# NvideaJetsonNano.net
KiCad netlist of a schematic drawn in Altium Designer
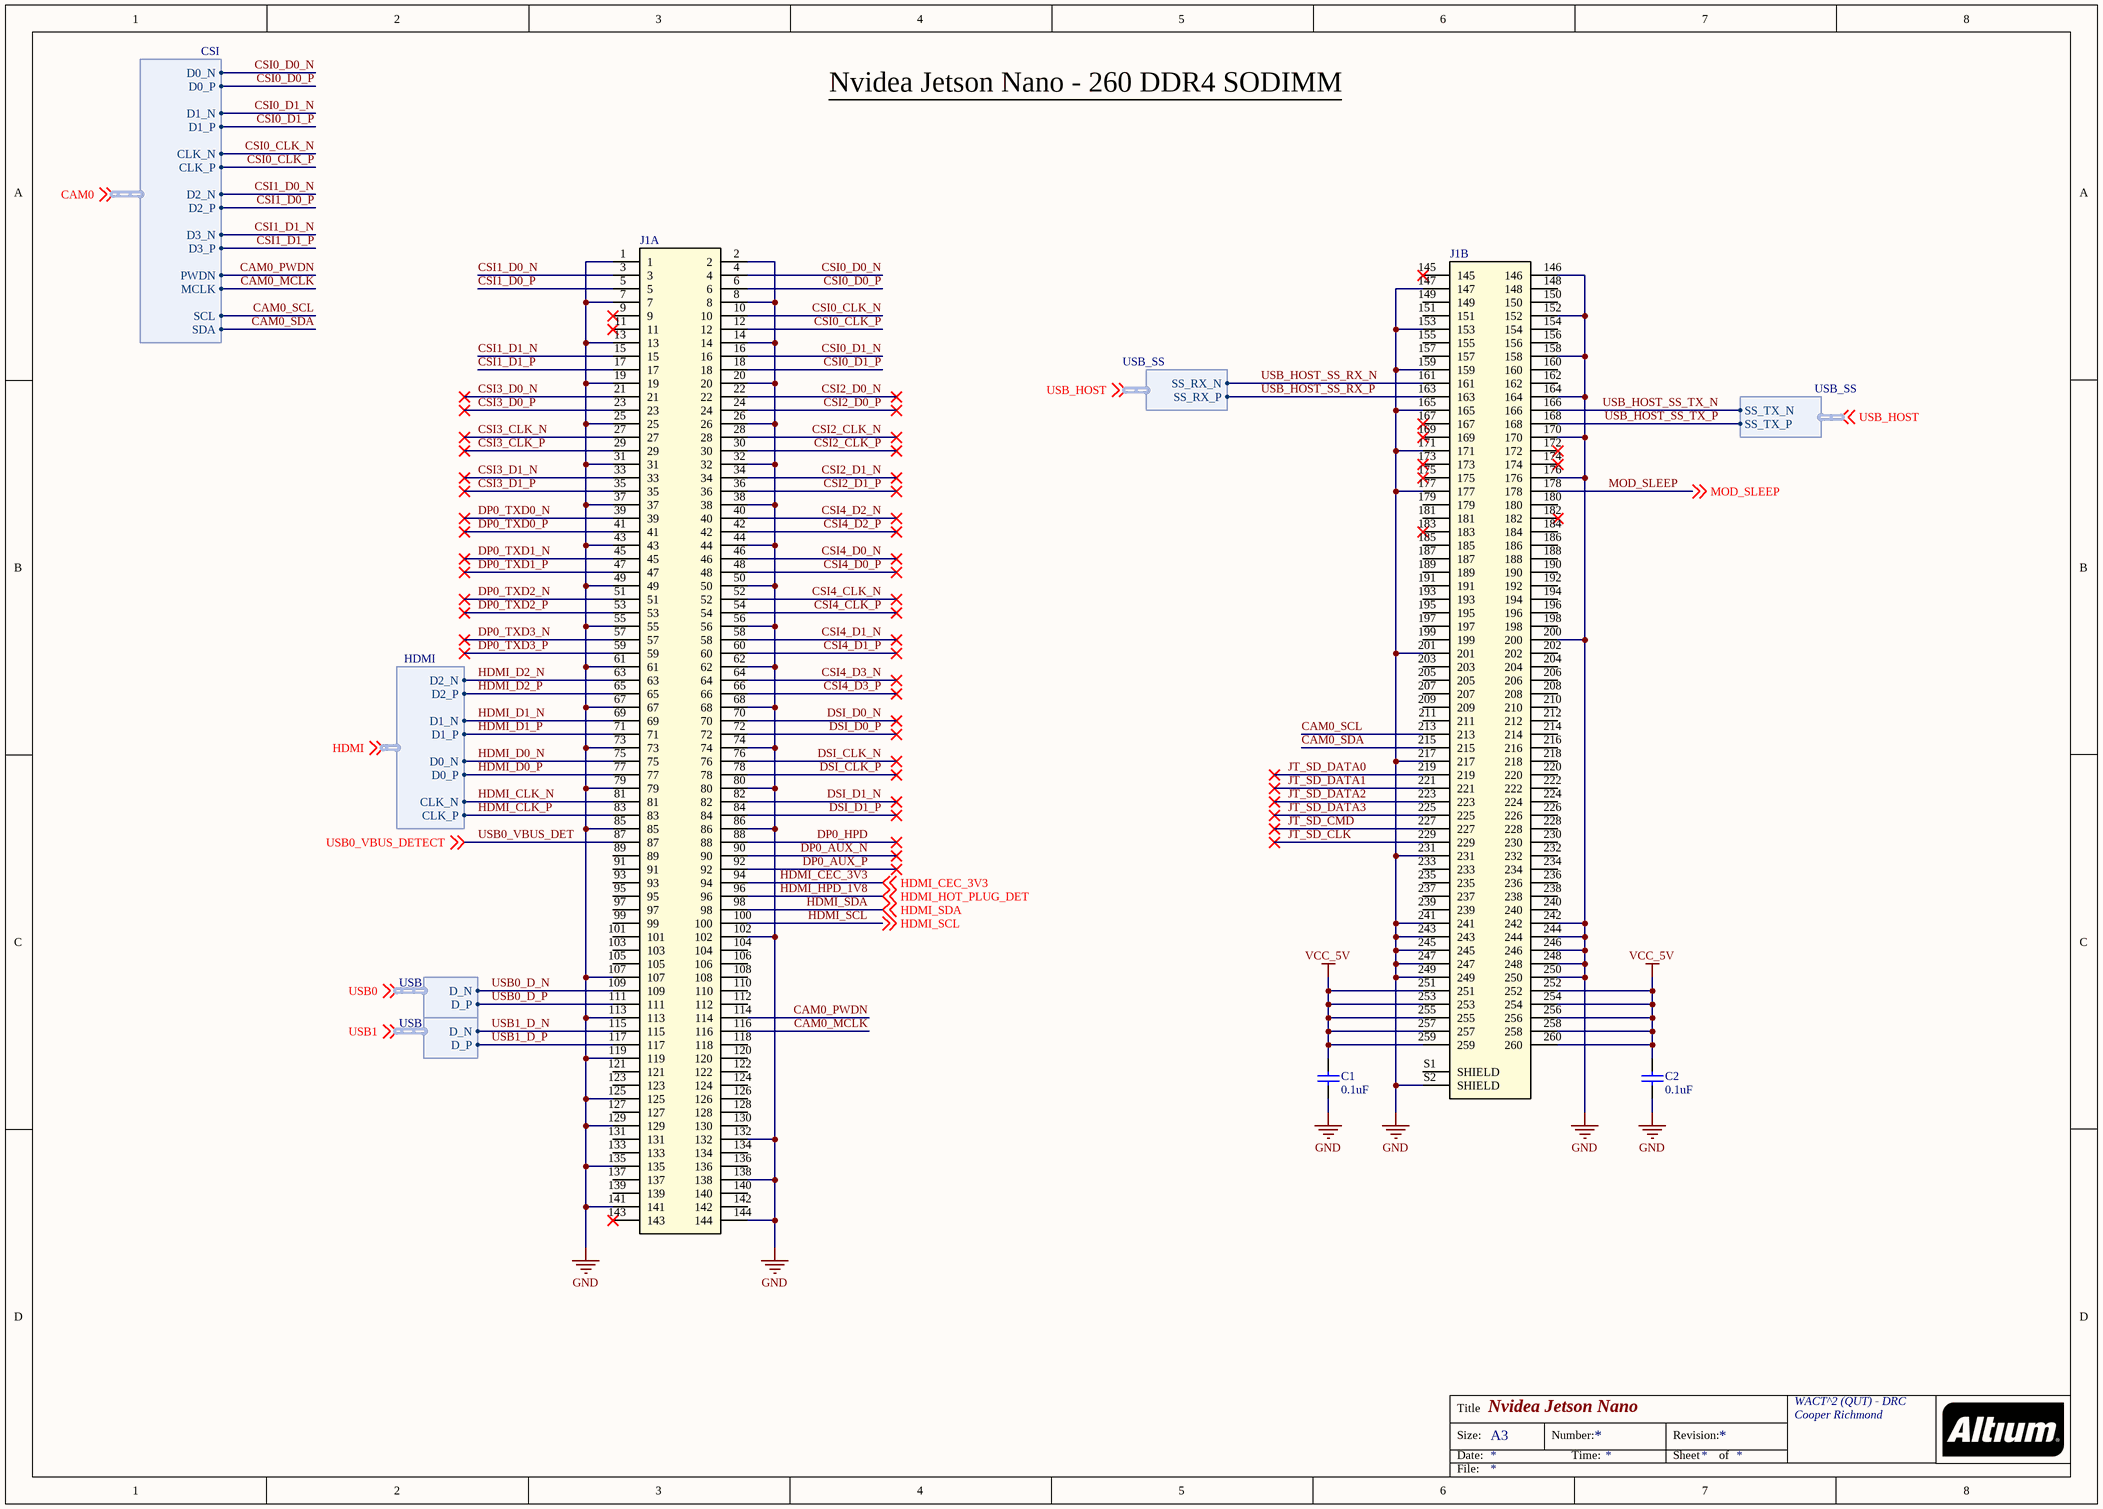
[diagram p0: NvideaJetsonNano.SchDoc]

(export (version "E")
  (design (tool "Eeschema 10.0.6"))
  (components
    (comp (ref "C1")
      (value "0.1uF")
      (footprint "C0402")
      (description "=Description")
      (fields (field (name "Comment") "CAP"))
      (libsource (lib "DRClib") (part "CAP"))
    )
    (comp (ref "C2")
      (value "0.1uF")
      (footprint "C0402")
      (description "=Description")
      (fields (field (name "Comment") "CAP"))
      (libsource (lib "DRClib") (part "CAP"))
    )
    (comp (ref "J1")
      (value "2309411-2")
      (footprint "TE_2309411")
      (description "DDR4 SODIMM 260P 8.0H STD")
      (fields (field (name "MF") "TE Connectivity"))
      (libsource (lib "DRClib") (part "2309411-2"))
    )
  )
  (nets
    (net (code "1") (name "/CAM0_MCLK") (class "Default")
      (node (ref "J1") (pin "116") (pinfunction "116_116") (pintype "passive"))
    )
    (net (code "2") (name "/CAM0_PWDN") (class "Default")
      (node (ref "J1") (pin "114") (pinfunction "114_114") (pintype "passive"))
    )
    (net (code "3") (name "/CAM0_SCL") (class "Default")
      (node (ref "J1") (pin "213") (pinfunction "213_213") (pintype "passive"))
    )
    (net (code "4") (name "/CAM0_SDA") (class "Default")
      (node (ref "J1") (pin "215") (pinfunction "215_215") (pintype "passive"))
    )
    (net (code "5") (name "/CSI0_CLK_N") (class "Default")
      (node (ref "J1") (pin "10") (pinfunction "10_10") (pintype "passive"))
    )
    (net (code "6") (name "/CSI0_CLK_P") (class "Default")
      (node (ref "J1") (pin "12") (pinfunction "12_12") (pintype "passive"))
    )
    (net (code "7") (name "/CSI0_D0_N") (class "Default")
      (node (ref "J1") (pin "4") (pinfunction "4_4") (pintype "passive"))
    )
    (net (code "8") (name "/CSI0_D0_P") (class "Default")
      (node (ref "J1") (pin "6") (pinfunction "6_6") (pintype "passive"))
    )
    (net (code "9") (name "/CSI0_D1_N") (class "Default")
      (node (ref "J1") (pin "16") (pinfunction "16_16") (pintype "passive"))
    )
    (net (code "10") (name "/CSI0_D1_P") (class "Default")
      (node (ref "J1") (pin "18") (pinfunction "18_18") (pintype "passive"))
    )
    (net (code "11") (name "/CSI1_D0_N") (class "Default")
      (node (ref "J1") (pin "3") (pinfunction "3_3") (pintype "passive"))
    )
    (net (code "12") (name "/CSI1_D0_P") (class "Default")
      (node (ref "J1") (pin "5") (pinfunction "5_5") (pintype "passive"))
    )
    (net (code "13") (name "/CSI1_D1_N") (class "Default")
      (node (ref "J1") (pin "15") (pinfunction "15_15") (pintype "passive"))
    )
    (net (code "14") (name "/CSI1_D1_P") (class "Default")
      (node (ref "J1") (pin "17") (pinfunction "17_17") (pintype "passive"))
    )
    (net (code "15") (name "/CSI2_CLK_N") (class "Default")
      (node (ref "J1") (pin "28") (pinfunction "28_28") (pintype "passive+no_connect"))
    )
    (net (code "16") (name "/CSI2_CLK_P") (class "Default")
      (node (ref "J1") (pin "30") (pinfunction "30_30") (pintype "passive+no_connect"))
    )
    (net (code "17") (name "/CSI2_D0_N") (class "Default")
      (node (ref "J1") (pin "22") (pinfunction "22_22") (pintype "passive+no_connect"))
    )
    (net (code "18") (name "/CSI2_D0_P") (class "Default")
      (node (ref "J1") (pin "24") (pinfunction "24_24") (pintype "passive+no_connect"))
    )
    (net (code "19") (name "/CSI2_D1_N") (class "Default")
      (node (ref "J1") (pin "34") (pinfunction "34_34") (pintype "passive+no_connect"))
    )
    (net (code "20") (name "/CSI2_D1_P") (class "Default")
      (node (ref "J1") (pin "36") (pinfunction "36_36") (pintype "passive+no_connect"))
    )
    (net (code "21") (name "/CSI3_CLK_N") (class "Default")
      (node (ref "J1") (pin "27") (pinfunction "27_27") (pintype "passive+no_connect"))
    )
    (net (code "22") (name "/CSI3_CLK_P") (class "Default")
      (node (ref "J1") (pin "29") (pinfunction "29_29") (pintype "passive+no_connect"))
    )
    (net (code "23") (name "/CSI3_D0_N") (class "Default")
      (node (ref "J1") (pin "21") (pinfunction "21_21") (pintype "passive+no_connect"))
    )
    (net (code "24") (name "/CSI3_D0_P") (class "Default")
      (node (ref "J1") (pin "23") (pinfunction "23_23") (pintype "passive+no_connect"))
    )
    (net (code "25") (name "/CSI3_D1_N") (class "Default")
      (node (ref "J1") (pin "33") (pinfunction "33_33") (pintype "passive+no_connect"))
    )
    (net (code "26") (name "/CSI3_D1_P") (class "Default")
      (node (ref "J1") (pin "35") (pinfunction "35_35") (pintype "passive+no_connect"))
    )
    (net (code "27") (name "/CSI4_CLK_N") (class "Default")
      (node (ref "J1") (pin "52") (pinfunction "52_52") (pintype "passive+no_connect"))
    )
    (net (code "28") (name "/CSI4_CLK_P") (class "Default")
      (node (ref "J1") (pin "54") (pinfunction "54_54") (pintype "passive+no_connect"))
    )
    (net (code "29") (name "/CSI4_D0_N") (class "Default")
      (node (ref "J1") (pin "46") (pinfunction "46_46") (pintype "passive+no_connect"))
    )
    (net (code "30") (name "/CSI4_D0_P") (class "Default")
      (node (ref "J1") (pin "48") (pinfunction "48_48") (pintype "passive+no_connect"))
    )
    (net (code "31") (name "/CSI4_D1_N") (class "Default")
      (node (ref "J1") (pin "58") (pinfunction "58_58") (pintype "passive+no_connect"))
    )
    (net (code "32") (name "/CSI4_D1_P") (class "Default")
      (node (ref "J1") (pin "60") (pinfunction "60_60") (pintype "passive+no_connect"))
    )
    (net (code "33") (name "/CSI4_D2_N") (class "Default")
      (node (ref "J1") (pin "40") (pinfunction "40_40") (pintype "passive+no_connect"))
    )
    (net (code "34") (name "/CSI4_D2_P") (class "Default")
      (node (ref "J1") (pin "42") (pinfunction "42_42") (pintype "passive+no_connect"))
    )
    (net (code "35") (name "/CSI4_D3_N") (class "Default")
      (node (ref "J1") (pin "64") (pinfunction "64_64") (pintype "passive+no_connect"))
    )
    (net (code "36") (name "/CSI4_D3_P") (class "Default")
      (node (ref "J1") (pin "66") (pinfunction "66_66") (pintype "passive+no_connect"))
    )
    (net (code "37") (name "/DP0_AUX_N") (class "Default")
      (node (ref "J1") (pin "90") (pinfunction "90_90") (pintype "passive+no_connect"))
    )
    (net (code "38") (name "/DP0_AUX_P") (class "Default")
      (node (ref "J1") (pin "92") (pinfunction "92_92") (pintype "passive+no_connect"))
    )
    (net (code "39") (name "/DP0_HPD") (class "Default")
      (node (ref "J1") (pin "88") (pinfunction "88_88") (pintype "passive+no_connect"))
    )
    (net (code "40") (name "/DP0_TXD0_N") (class "Default")
      (node (ref "J1") (pin "39") (pinfunction "39_39") (pintype "passive+no_connect"))
    )
    (net (code "41") (name "/DP0_TXD0_P") (class "Default")
      (node (ref "J1") (pin "41") (pinfunction "41_41") (pintype "passive+no_connect"))
    )
    (net (code "42") (name "/DP0_TXD1_N") (class "Default")
      (node (ref "J1") (pin "45") (pinfunction "45_45") (pintype "passive+no_connect"))
    )
    (net (code "43") (name "/DP0_TXD1_P") (class "Default")
      (node (ref "J1") (pin "47") (pinfunction "47_47") (pintype "passive+no_connect"))
    )
    (net (code "44") (name "/DP0_TXD2_N") (class "Default")
      (node (ref "J1") (pin "51") (pinfunction "51_51") (pintype "passive+no_connect"))
    )
    (net (code "45") (name "/DP0_TXD2_P") (class "Default")
      (node (ref "J1") (pin "53") (pinfunction "53_53") (pintype "passive+no_connect"))
    )
    (net (code "46") (name "/DP0_TXD3_N") (class "Default")
      (node (ref "J1") (pin "57") (pinfunction "57_57") (pintype "passive+no_connect"))
    )
    (net (code "47") (name "/DP0_TXD3_P") (class "Default")
      (node (ref "J1") (pin "59") (pinfunction "59_59") (pintype "passive+no_connect"))
    )
    (net (code "48") (name "/DSI_CLK_N") (class "Default")
      (node (ref "J1") (pin "76") (pinfunction "76_76") (pintype "passive+no_connect"))
    )
    (net (code "49") (name "/DSI_CLK_P") (class "Default")
      (node (ref "J1") (pin "78") (pinfunction "78_78") (pintype "passive+no_connect"))
    )
    (net (code "50") (name "/DSI_D0_N") (class "Default")
      (node (ref "J1") (pin "70") (pinfunction "70_70") (pintype "passive+no_connect"))
    )
    (net (code "51") (name "/DSI_D0_P") (class "Default")
      (node (ref "J1") (pin "72") (pinfunction "72_72") (pintype "passive+no_connect"))
    )
    (net (code "52") (name "/DSI_D1_N") (class "Default")
      (node (ref "J1") (pin "82") (pinfunction "82_82") (pintype "passive+no_connect"))
    )
    (net (code "53") (name "/DSI_D1_P") (class "Default")
      (node (ref "J1") (pin "84") (pinfunction "84_84") (pintype "passive+no_connect"))
    )
    (net (code "54") (name "/HDMI_CLK_N") (class "Default")
      (node (ref "J1") (pin "81") (pinfunction "81_81") (pintype "passive"))
    )
    (net (code "55") (name "/HDMI_CLK_P") (class "Default")
      (node (ref "J1") (pin "83") (pinfunction "83_83") (pintype "passive"))
    )
    (net (code "56") (name "/HDMI_D0_N") (class "Default")
      (node (ref "J1") (pin "75") (pinfunction "75_75") (pintype "passive"))
    )
    (net (code "57") (name "/HDMI_D0_P") (class "Default")
      (node (ref "J1") (pin "77") (pinfunction "77_77") (pintype "passive"))
    )
    (net (code "58") (name "/HDMI_D1_N") (class "Default")
      (node (ref "J1") (pin "69") (pinfunction "69_69") (pintype "passive"))
    )
    (net (code "59") (name "/HDMI_D1_P") (class "Default")
      (node (ref "J1") (pin "71") (pinfunction "71_71") (pintype "passive"))
    )
    (net (code "60") (name "/HDMI_D2_N") (class "Default")
      (node (ref "J1") (pin "63") (pinfunction "63_63") (pintype "passive"))
    )
    (net (code "61") (name "/HDMI_D2_P") (class "Default")
      (node (ref "J1") (pin "65") (pinfunction "65_65") (pintype "passive"))
    )
    (net (code "62") (name "/JT_SD_CLK") (class "Default")
      (node (ref "J1") (pin "229") (pinfunction "229_229") (pintype "passive+no_connect"))
    )
    (net (code "63") (name "/JT_SD_CMD") (class "Default")
      (node (ref "J1") (pin "227") (pinfunction "227_227") (pintype "passive+no_connect"))
    )
    (net (code "64") (name "/JT_SD_DATA0") (class "Default")
      (node (ref "J1") (pin "219") (pinfunction "219_219") (pintype "passive+no_connect"))
    )
    (net (code "65") (name "/JT_SD_DATA1") (class "Default")
      (node (ref "J1") (pin "221") (pinfunction "221_221") (pintype "passive+no_connect"))
    )
    (net (code "66") (name "/JT_SD_DATA2") (class "Default")
      (node (ref "J1") (pin "223") (pinfunction "223_223") (pintype "passive+no_connect"))
    )
    (net (code "67") (name "/JT_SD_DATA3") (class "Default")
      (node (ref "J1") (pin "225") (pinfunction "225_225") (pintype "passive+no_connect"))
    )
    (net (code "68") (name "/USB0_D_N") (class "Default")
      (node (ref "J1") (pin "109") (pinfunction "109_109") (pintype "passive"))
    )
    (net (code "69") (name "/USB0_D_P") (class "Default")
      (node (ref "J1") (pin "111") (pinfunction "111_111") (pintype "passive"))
    )
    (net (code "70") (name "/USB1_D_N") (class "Default")
      (node (ref "J1") (pin "115") (pinfunction "115_115") (pintype "passive"))
    )
    (net (code "71") (name "/USB1_D_P") (class "Default")
      (node (ref "J1") (pin "117") (pinfunction "117_117") (pintype "passive"))
    )
    (net (code "72") (name "/USB_HOST_SS_RX_N") (class "Default")
      (node (ref "J1") (pin "161") (pinfunction "161_161") (pintype "passive"))
    )
    (net (code "73") (name "/USB_HOST_SS_RX_P") (class "Default")
      (node (ref "J1") (pin "163") (pinfunction "163_163") (pintype "passive"))
    )
    (net (code "74") (name "/USB_HOST_SS_TX_N") (class "Default")
      (node (ref "J1") (pin "166") (pinfunction "166_166") (pintype "passive"))
    )
    (net (code "75") (name "/USB_HOST_SS_TX_P") (class "Default")
      (node (ref "J1") (pin "168") (pinfunction "168_168") (pintype "passive"))
    )
    (net (code "77") (name "GND") (class "Default")
      (node (ref "C1") (pin "2") (pinfunction "2_2") (pintype "passive"))
      (node (ref "C2") (pin "2") (pinfunction "2_2") (pintype "passive"))
      (node (ref "J1") (pin "1") (pinfunction "1_1") (pintype "passive"))
      (node (ref "J1") (pin "102") (pinfunction "102_102") (pintype "passive"))
      (node (ref "J1") (pin "107") (pinfunction "107_107") (pintype "passive"))
      (node (ref "J1") (pin "113") (pinfunction "113_113") (pintype "passive"))
      (node (ref "J1") (pin "119") (pinfunction "119_119") (pintype "passive"))
      (node (ref "J1") (pin "125") (pinfunction "125_125") (pintype "passive"))
      (node (ref "J1") (pin "129") (pinfunction "129_129") (pintype "passive"))
      (node (ref "J1") (pin "13") (pinfunction "13_13") (pintype "passive"))
      (node (ref "J1") (pin "132") (pinfunction "132_132") (pintype "passive"))
      (node (ref "J1") (pin "135") (pinfunction "135_135") (pintype "passive"))
      (node (ref "J1") (pin "138") (pinfunction "138_138") (pintype "passive"))
      (node (ref "J1") (pin "14") (pinfunction "14_14") (pintype "passive"))
      (node (ref "J1") (pin "141") (pinfunction "141_141") (pintype "passive"))
      (node (ref "J1") (pin "144") (pinfunction "144_144") (pintype "passive"))
      (node (ref "J1") (pin "146") (pinfunction "146_146") (pintype "passive"))
      (node (ref "J1") (pin "147") (pinfunction "147_147") (pintype "passive"))
      (node (ref "J1") (pin "152") (pinfunction "152_152") (pintype "passive"))
      (node (ref "J1") (pin "153") (pinfunction "153_153") (pintype "passive"))
      (node (ref "J1") (pin "158") (pinfunction "158_158") (pintype "passive"))
      (node (ref "J1") (pin "159") (pinfunction "159_159") (pintype "passive"))
      (node (ref "J1") (pin "164") (pinfunction "164_164") (pintype "passive"))
      (node (ref "J1") (pin "165") (pinfunction "165_165") (pintype "passive"))
      (node (ref "J1") (pin "170") (pinfunction "170_170") (pintype "passive"))
      (node (ref "J1") (pin "171") (pinfunction "171_171") (pintype "passive"))
      (node (ref "J1") (pin "176") (pinfunction "176_176") (pintype "passive"))
      (node (ref "J1") (pin "177") (pinfunction "177_177") (pintype "passive"))
      (node (ref "J1") (pin "19") (pinfunction "19_19") (pintype "passive"))
      (node (ref "J1") (pin "2") (pinfunction "2_2") (pintype "passive"))
      (node (ref "J1") (pin "20") (pinfunction "20_20") (pintype "passive"))
      (node (ref "J1") (pin "200") (pinfunction "200_200") (pintype "passive"))
      (node (ref "J1") (pin "201") (pinfunction "201_201") (pintype "passive"))
      (node (ref "J1") (pin "217") (pinfunction "217_217") (pintype "passive"))
      (node (ref "J1") (pin "231") (pinfunction "231_231") (pintype "passive"))
      (node (ref "J1") (pin "241") (pinfunction "241_241") (pintype "passive"))
      (node (ref "J1") (pin "242") (pinfunction "242_242") (pintype "passive"))
      (node (ref "J1") (pin "243") (pinfunction "243_243") (pintype "passive"))
      (node (ref "J1") (pin "244") (pinfunction "244_244") (pintype "passive"))
      (node (ref "J1") (pin "245") (pinfunction "245_245") (pintype "passive"))
      (node (ref "J1") (pin "246") (pinfunction "246_246") (pintype "passive"))
      (node (ref "J1") (pin "247") (pinfunction "247_247") (pintype "passive"))
      (node (ref "J1") (pin "248") (pinfunction "248_248") (pintype "passive"))
      (node (ref "J1") (pin "249") (pinfunction "249_249") (pintype "passive"))
      (node (ref "J1") (pin "25") (pinfunction "25_25") (pintype "passive"))
      (node (ref "J1") (pin "250") (pinfunction "250_250") (pintype "passive"))
      (node (ref "J1") (pin "26") (pinfunction "26_26") (pintype "passive"))
      (node (ref "J1") (pin "31") (pinfunction "31_31") (pintype "passive"))
      (node (ref "J1") (pin "32") (pinfunction "32_32") (pintype "passive"))
      (node (ref "J1") (pin "37") (pinfunction "37_37") (pintype "passive"))
      (node (ref "J1") (pin "38") (pinfunction "38_38") (pintype "passive"))
      (node (ref "J1") (pin "43") (pinfunction "43_43") (pintype "passive"))
      (node (ref "J1") (pin "44") (pinfunction "44_44") (pintype "passive"))
      (node (ref "J1") (pin "49") (pinfunction "49_49") (pintype "passive"))
      (node (ref "J1") (pin "50") (pinfunction "50_50") (pintype "passive"))
      (node (ref "J1") (pin "55") (pinfunction "55_55") (pintype "passive"))
      (node (ref "J1") (pin "56") (pinfunction "56_56") (pintype "passive"))
      (node (ref "J1") (pin "61") (pinfunction "61_61") (pintype "passive"))
      (node (ref "J1") (pin "62") (pinfunction "62_62") (pintype "passive"))
      (node (ref "J1") (pin "67") (pinfunction "67_67") (pintype "passive"))
      (node (ref "J1") (pin "68") (pinfunction "68_68") (pintype "passive"))
      (node (ref "J1") (pin "7") (pinfunction "7_7") (pintype "passive"))
      (node (ref "J1") (pin "73") (pinfunction "73_73") (pintype "passive"))
      (node (ref "J1") (pin "74") (pinfunction "74_74") (pintype "passive"))
      (node (ref "J1") (pin "79") (pinfunction "79_79") (pintype "passive"))
      (node (ref "J1") (pin "8") (pinfunction "8_8") (pintype "passive"))
      (node (ref "J1") (pin "80") (pinfunction "80_80") (pintype "passive"))
      (node (ref "J1") (pin "85") (pinfunction "85_85") (pintype "passive"))
      (node (ref "J1") (pin "86") (pinfunction "86_86") (pintype "passive"))
      (node (ref "J1") (pin "S2") (pinfunction "SHIELD_S2") (pintype "passive"))
    )
    (net (code "79") (name "HDMI_CEC_3V3") (class "Default")
      (node (ref "J1") (pin "94") (pinfunction "94_94") (pintype "passive"))
    )
    (net (code "80") (name "HDMI_HOT_PLUG_DET") (class "Default")
      (node (ref "J1") (pin "96") (pinfunction "96_96") (pintype "passive"))
    )
    (net (code "81") (name "HDMI_SCL") (class "Default")
      (node (ref "J1") (pin "100") (pinfunction "100_100") (pintype "passive"))
    )
    (net (code "82") (name "HDMI_SDA") (class "Default")
      (node (ref "J1") (pin "98") (pinfunction "98_98") (pintype "passive"))
    )
    (net (code "83") (name "MOD_SLEEP") (class "Default")
      (node (ref "J1") (pin "178") (pinfunction "178_178") (pintype "passive"))
    )
    (net (code "85") (name "USB0_VBUS_DETECT") (class "Default")
      (node (ref "J1") (pin "87") (pinfunction "87_87") (pintype "passive"))
    )
    (net (code "88") (name "VCC_5V") (class "Default")
      (node (ref "C1") (pin "1") (pinfunction "1_1") (pintype "passive"))
      (node (ref "C2") (pin "1") (pinfunction "1_1") (pintype "passive"))
      (node (ref "J1") (pin "251") (pinfunction "251_251") (pintype "passive"))
      (node (ref "J1") (pin "252") (pinfunction "252_252") (pintype "passive"))
      (node (ref "J1") (pin "253") (pinfunction "253_253") (pintype "passive"))
      (node (ref "J1") (pin "254") (pinfunction "254_254") (pintype "passive"))
      (node (ref "J1") (pin "255") (pinfunction "255_255") (pintype "passive"))
      (node (ref "J1") (pin "256") (pinfunction "256_256") (pintype "passive"))
      (node (ref "J1") (pin "257") (pinfunction "257_257") (pintype "passive"))
      (node (ref "J1") (pin "258") (pinfunction "258_258") (pintype "passive"))
      (node (ref "J1") (pin "259") (pinfunction "259_259") (pintype "passive"))
      (node (ref "J1") (pin "260") (pinfunction "260_260") (pintype "passive"))
    )
    (net (code "89") (name "unconnected-(J1-Pad9)") (class "Default")
      (node (ref "J1") (pin "9") (pinfunction "9_9") (pintype "passive+no_connect"))
    )
    (net (code "90") (name "unconnected-(J1-Pad11)") (class "Default")
      (node (ref "J1") (pin "11") (pinfunction "11_11") (pintype "passive+no_connect"))
    )
    (net (code "91") (name "unconnected-(J1-Pad89)") (class "Default")
      (node (ref "J1") (pin "89") (pinfunction "89_89") (pintype "passive"))
    )
    (net (code "92") (name "unconnected-(J1-Pad91)") (class "Default")
      (node (ref "J1") (pin "91") (pinfunction "91_91") (pintype "passive"))
    )
    (net (code "93") (name "unconnected-(J1-Pad93)") (class "Default")
      (node (ref "J1") (pin "93") (pinfunction "93_93") (pintype "passive"))
    )
    (net (code "94") (name "unconnected-(J1-Pad95)") (class "Default")
      (node (ref "J1") (pin "95") (pinfunction "95_95") (pintype "passive"))
    )
    (net (code "95") (name "unconnected-(J1-Pad97)") (class "Default")
      (node (ref "J1") (pin "97") (pinfunction "97_97") (pintype "passive"))
    )
    (net (code "96") (name "unconnected-(J1-Pad99)") (class "Default")
      (node (ref "J1") (pin "99") (pinfunction "99_99") (pintype "passive"))
    )
    (net (code "97") (name "unconnected-(J1-Pad101)") (class "Default")
      (node (ref "J1") (pin "101") (pinfunction "101_101") (pintype "passive"))
    )
    (net (code "98") (name "unconnected-(J1-Pad103)") (class "Default")
      (node (ref "J1") (pin "103") (pinfunction "103_103") (pintype "passive"))
    )
    (net (code "99") (name "unconnected-(J1-Pad104)") (class "Default")
      (node (ref "J1") (pin "104") (pinfunction "104_104") (pintype "passive"))
    )
    (net (code "100") (name "unconnected-(J1-Pad105)") (class "Default")
      (node (ref "J1") (pin "105") (pinfunction "105_105") (pintype "passive"))
    )
    (net (code "101") (name "unconnected-(J1-Pad106)") (class "Default")
      (node (ref "J1") (pin "106") (pinfunction "106_106") (pintype "passive"))
    )
    (net (code "102") (name "unconnected-(J1-Pad108)") (class "Default")
      (node (ref "J1") (pin "108") (pinfunction "108_108") (pintype "passive"))
    )
    (net (code "103") (name "unconnected-(J1-Pad110)") (class "Default")
      (node (ref "J1") (pin "110") (pinfunction "110_110") (pintype "passive"))
    )
    (net (code "104") (name "unconnected-(J1-Pad112)") (class "Default")
      (node (ref "J1") (pin "112") (pinfunction "112_112") (pintype "passive"))
    )
    (net (code "105") (name "unconnected-(J1-Pad118)") (class "Default")
      (node (ref "J1") (pin "118") (pinfunction "118_118") (pintype "passive"))
    )
    (net (code "106") (name "unconnected-(J1-Pad120)") (class "Default")
      (node (ref "J1") (pin "120") (pinfunction "120_120") (pintype "passive"))
    )
    (net (code "107") (name "unconnected-(J1-Pad121)") (class "Default")
      (node (ref "J1") (pin "121") (pinfunction "121_121") (pintype "passive"))
    )
    (net (code "108") (name "unconnected-(J1-Pad122)") (class "Default")
      (node (ref "J1") (pin "122") (pinfunction "122_122") (pintype "passive"))
    )
    (net (code "109") (name "unconnected-(J1-Pad123)") (class "Default")
      (node (ref "J1") (pin "123") (pinfunction "123_123") (pintype "passive"))
    )
    (net (code "110") (name "unconnected-(J1-Pad124)") (class "Default")
      (node (ref "J1") (pin "124") (pinfunction "124_124") (pintype "passive"))
    )
    (net (code "111") (name "unconnected-(J1-Pad126)") (class "Default")
      (node (ref "J1") (pin "126") (pinfunction "126_126") (pintype "passive"))
    )
    (net (code "112") (name "unconnected-(J1-Pad127)") (class "Default")
      (node (ref "J1") (pin "127") (pinfunction "127_127") (pintype "passive"))
    )
    (net (code "113") (name "unconnected-(J1-Pad128)") (class "Default")
      (node (ref "J1") (pin "128") (pinfunction "128_128") (pintype "passive"))
    )
    (net (code "114") (name "unconnected-(J1-Pad130)") (class "Default")
      (node (ref "J1") (pin "130") (pinfunction "130_130") (pintype "passive"))
    )
    (net (code "115") (name "unconnected-(J1-Pad131)") (class "Default")
      (node (ref "J1") (pin "131") (pinfunction "131_131") (pintype "passive"))
    )
    (net (code "116") (name "unconnected-(J1-Pad133)") (class "Default")
      (node (ref "J1") (pin "133") (pinfunction "133_133") (pintype "passive"))
    )
    (net (code "117") (name "unconnected-(J1-Pad134)") (class "Default")
      (node (ref "J1") (pin "134") (pinfunction "134_134") (pintype "passive"))
    )
    (net (code "118") (name "unconnected-(J1-Pad136)") (class "Default")
      (node (ref "J1") (pin "136") (pinfunction "136_136") (pintype "passive"))
    )
    (net (code "119") (name "unconnected-(J1-Pad137)") (class "Default")
      (node (ref "J1") (pin "137") (pinfunction "137_137") (pintype "passive"))
    )
    (net (code "120") (name "unconnected-(J1-Pad139)") (class "Default")
      (node (ref "J1") (pin "139") (pinfunction "139_139") (pintype "passive"))
    )
    (net (code "121") (name "unconnected-(J1-Pad140)") (class "Default")
      (node (ref "J1") (pin "140") (pinfunction "140_140") (pintype "passive"))
    )
    (net (code "122") (name "unconnected-(J1-Pad142)") (class "Default")
      (node (ref "J1") (pin "142") (pinfunction "142_142") (pintype "passive"))
    )
    (net (code "123") (name "unconnected-(J1-Pad143)") (class "Default")
      (node (ref "J1") (pin "143") (pinfunction "143_143") (pintype "passive+no_connect"))
    )
    (net (code "124") (name "unconnected-(J1-Pad145)") (class "Default")
      (node (ref "J1") (pin "145") (pinfunction "145_145") (pintype "passive+no_connect"))
    )
    (net (code "125") (name "unconnected-(J1-Pad148)") (class "Default")
      (node (ref "J1") (pin "148") (pinfunction "148_148") (pintype "passive"))
    )
    (net (code "126") (name "unconnected-(J1-Pad149)") (class "Default")
      (node (ref "J1") (pin "149") (pinfunction "149_149") (pintype "passive"))
    )
    (net (code "127") (name "unconnected-(J1-Pad150)") (class "Default")
      (node (ref "J1") (pin "150") (pinfunction "150_150") (pintype "passive"))
    )
    (net (code "128") (name "unconnected-(J1-Pad151)") (class "Default")
      (node (ref "J1") (pin "151") (pinfunction "151_151") (pintype "passive"))
    )
    (net (code "129") (name "unconnected-(J1-Pad154)") (class "Default")
      (node (ref "J1") (pin "154") (pinfunction "154_154") (pintype "passive"))
    )
    (net (code "130") (name "unconnected-(J1-Pad155)") (class "Default")
      (node (ref "J1") (pin "155") (pinfunction "155_155") (pintype "passive"))
    )
    (net (code "131") (name "unconnected-(J1-Pad156)") (class "Default")
      (node (ref "J1") (pin "156") (pinfunction "156_156") (pintype "passive"))
    )
    (net (code "132") (name "unconnected-(J1-Pad157)") (class "Default")
      (node (ref "J1") (pin "157") (pinfunction "157_157") (pintype "passive"))
    )
    (net (code "133") (name "unconnected-(J1-Pad160)") (class "Default")
      (node (ref "J1") (pin "160") (pinfunction "160_160") (pintype "passive"))
    )
    (net (code "134") (name "unconnected-(J1-Pad162)") (class "Default")
      (node (ref "J1") (pin "162") (pinfunction "162_162") (pintype "passive"))
    )
    (net (code "135") (name "unconnected-(J1-Pad167)") (class "Default")
      (node (ref "J1") (pin "167") (pinfunction "167_167") (pintype "passive+no_connect"))
    )
    (net (code "136") (name "unconnected-(J1-Pad169)") (class "Default")
      (node (ref "J1") (pin "169") (pinfunction "169_169") (pintype "passive+no_connect"))
    )
    (net (code "137") (name "unconnected-(J1-Pad172)") (class "Default")
      (node (ref "J1") (pin "172") (pinfunction "172_172") (pintype "passive+no_connect"))
    )
    (net (code "138") (name "unconnected-(J1-Pad173)") (class "Default")
      (node (ref "J1") (pin "173") (pinfunction "173_173") (pintype "passive+no_connect"))
    )
    (net (code "139") (name "unconnected-(J1-Pad174)") (class "Default")
      (node (ref "J1") (pin "174") (pinfunction "174_174") (pintype "passive+no_connect"))
    )
    (net (code "140") (name "unconnected-(J1-Pad175)") (class "Default")
      (node (ref "J1") (pin "175") (pinfunction "175_175") (pintype "passive+no_connect"))
    )
    (net (code "141") (name "unconnected-(J1-Pad179)") (class "Default")
      (node (ref "J1") (pin "179") (pinfunction "179_179") (pintype "passive"))
    )
    (net (code "142") (name "unconnected-(J1-Pad180)") (class "Default")
      (node (ref "J1") (pin "180") (pinfunction "180_180") (pintype "passive"))
    )
    (net (code "143") (name "unconnected-(J1-Pad181)") (class "Default")
      (node (ref "J1") (pin "181") (pinfunction "181_181") (pintype "passive"))
    )
    (net (code "144") (name "unconnected-(J1-Pad182)") (class "Default")
      (node (ref "J1") (pin "182") (pinfunction "182_182") (pintype "passive+no_connect"))
    )
    (net (code "145") (name "unconnected-(J1-Pad183)") (class "Default")
      (node (ref "J1") (pin "183") (pinfunction "183_183") (pintype "passive+no_connect"))
    )
    (net (code "146") (name "unconnected-(J1-Pad184)") (class "Default")
      (node (ref "J1") (pin "184") (pinfunction "184_184") (pintype "passive"))
    )
    (net (code "147") (name "unconnected-(J1-Pad185)") (class "Default")
      (node (ref "J1") (pin "185") (pinfunction "185_185") (pintype "passive"))
    )
    (net (code "148") (name "unconnected-(J1-Pad186)") (class "Default")
      (node (ref "J1") (pin "186") (pinfunction "186_186") (pintype "passive"))
    )
    (net (code "149") (name "unconnected-(J1-Pad187)") (class "Default")
      (node (ref "J1") (pin "187") (pinfunction "187_187") (pintype "passive"))
    )
    (net (code "150") (name "unconnected-(J1-Pad188)") (class "Default")
      (node (ref "J1") (pin "188") (pinfunction "188_188") (pintype "passive"))
    )
    (net (code "151") (name "unconnected-(J1-Pad189)") (class "Default")
      (node (ref "J1") (pin "189") (pinfunction "189_189") (pintype "passive"))
    )
    (net (code "152") (name "unconnected-(J1-Pad190)") (class "Default")
      (node (ref "J1") (pin "190") (pinfunction "190_190") (pintype "passive"))
    )
    (net (code "153") (name "unconnected-(J1-Pad191)") (class "Default")
      (node (ref "J1") (pin "191") (pinfunction "191_191") (pintype "passive"))
    )
    (net (code "154") (name "unconnected-(J1-Pad192)") (class "Default")
      (node (ref "J1") (pin "192") (pinfunction "192_192") (pintype "passive"))
    )
    (net (code "155") (name "unconnected-(J1-Pad193)") (class "Default")
      (node (ref "J1") (pin "193") (pinfunction "193_193") (pintype "passive"))
    )
    (net (code "156") (name "unconnected-(J1-Pad194)") (class "Default")
      (node (ref "J1") (pin "194") (pinfunction "194_194") (pintype "passive"))
    )
    (net (code "157") (name "unconnected-(J1-Pad195)") (class "Default")
      (node (ref "J1") (pin "195") (pinfunction "195_195") (pintype "passive"))
    )
    (net (code "158") (name "unconnected-(J1-Pad196)") (class "Default")
      (node (ref "J1") (pin "196") (pinfunction "196_196") (pintype "passive"))
    )
    (net (code "159") (name "unconnected-(J1-Pad197)") (class "Default")
      (node (ref "J1") (pin "197") (pinfunction "197_197") (pintype "passive"))
    )
    (net (code "160") (name "unconnected-(J1-Pad198)") (class "Default")
      (node (ref "J1") (pin "198") (pinfunction "198_198") (pintype "passive"))
    )
    (net (code "161") (name "unconnected-(J1-Pad199)") (class "Default")
      (node (ref "J1") (pin "199") (pinfunction "199_199") (pintype "passive"))
    )
    (net (code "162") (name "unconnected-(J1-Pad202)") (class "Default")
      (node (ref "J1") (pin "202") (pinfunction "202_202") (pintype "passive"))
    )
    (net (code "163") (name "unconnected-(J1-Pad203)") (class "Default")
      (node (ref "J1") (pin "203") (pinfunction "203_203") (pintype "passive"))
    )
    (net (code "164") (name "unconnected-(J1-Pad204)") (class "Default")
      (node (ref "J1") (pin "204") (pinfunction "204_204") (pintype "passive"))
    )
    (net (code "165") (name "unconnected-(J1-Pad205)") (class "Default")
      (node (ref "J1") (pin "205") (pinfunction "205_205") (pintype "passive"))
    )
    (net (code "166") (name "unconnected-(J1-Pad206)") (class "Default")
      (node (ref "J1") (pin "206") (pinfunction "206_206") (pintype "passive"))
    )
    (net (code "167") (name "unconnected-(J1-Pad207)") (class "Default")
      (node (ref "J1") (pin "207") (pinfunction "207_207") (pintype "passive"))
    )
    (net (code "168") (name "unconnected-(J1-Pad208)") (class "Default")
      (node (ref "J1") (pin "208") (pinfunction "208_208") (pintype "passive"))
    )
    (net (code "169") (name "unconnected-(J1-Pad209)") (class "Default")
      (node (ref "J1") (pin "209") (pinfunction "209_209") (pintype "passive"))
    )
    (net (code "170") (name "unconnected-(J1-Pad210)") (class "Default")
      (node (ref "J1") (pin "210") (pinfunction "210_210") (pintype "passive"))
    )
    (net (code "171") (name "unconnected-(J1-Pad211)") (class "Default")
      (node (ref "J1") (pin "211") (pinfunction "211_211") (pintype "passive"))
    )
    (net (code "172") (name "unconnected-(J1-Pad212)") (class "Default")
      (node (ref "J1") (pin "212") (pinfunction "212_212") (pintype "passive"))
    )
    (net (code "173") (name "unconnected-(J1-Pad214)") (class "Default")
      (node (ref "J1") (pin "214") (pinfunction "214_214") (pintype "passive"))
    )
    (net (code "174") (name "unconnected-(J1-Pad216)") (class "Default")
      (node (ref "J1") (pin "216") (pinfunction "216_216") (pintype "passive"))
    )
    (net (code "175") (name "unconnected-(J1-Pad218)") (class "Default")
      (node (ref "J1") (pin "218") (pinfunction "218_218") (pintype "passive"))
    )
    (net (code "176") (name "unconnected-(J1-Pad220)") (class "Default")
      (node (ref "J1") (pin "220") (pinfunction "220_220") (pintype "passive"))
    )
    (net (code "177") (name "unconnected-(J1-Pad222)") (class "Default")
      (node (ref "J1") (pin "222") (pinfunction "222_222") (pintype "passive"))
    )
    (net (code "178") (name "unconnected-(J1-Pad224)") (class "Default")
      (node (ref "J1") (pin "224") (pinfunction "224_224") (pintype "passive"))
    )
    (net (code "179") (name "unconnected-(J1-Pad226)") (class "Default")
      (node (ref "J1") (pin "226") (pinfunction "226_226") (pintype "passive"))
    )
    (net (code "180") (name "unconnected-(J1-Pad228)") (class "Default")
      (node (ref "J1") (pin "228") (pinfunction "228_228") (pintype "passive"))
    )
    (net (code "181") (name "unconnected-(J1-Pad230)") (class "Default")
      (node (ref "J1") (pin "230") (pinfunction "230_230") (pintype "passive"))
    )
    (net (code "182") (name "unconnected-(J1-Pad232)") (class "Default")
      (node (ref "J1") (pin "232") (pinfunction "232_232") (pintype "passive"))
    )
    (net (code "183") (name "unconnected-(J1-Pad233)") (class "Default")
      (node (ref "J1") (pin "233") (pinfunction "233_233") (pintype "passive"))
    )
    (net (code "184") (name "unconnected-(J1-Pad234)") (class "Default")
      (node (ref "J1") (pin "234") (pinfunction "234_234") (pintype "passive"))
    )
    (net (code "185") (name "unconnected-(J1-Pad235)") (class "Default")
      (node (ref "J1") (pin "235") (pinfunction "235_235") (pintype "passive"))
    )
    (net (code "186") (name "unconnected-(J1-Pad236)") (class "Default")
      (node (ref "J1") (pin "236") (pinfunction "236_236") (pintype "passive"))
    )
    (net (code "187") (name "unconnected-(J1-Pad237)") (class "Default")
      (node (ref "J1") (pin "237") (pinfunction "237_237") (pintype "passive"))
    )
    (net (code "188") (name "unconnected-(J1-Pad238)") (class "Default")
      (node (ref "J1") (pin "238") (pinfunction "238_238") (pintype "passive"))
    )
    (net (code "189") (name "unconnected-(J1-Pad239)") (class "Default")
      (node (ref "J1") (pin "239") (pinfunction "239_239") (pintype "passive"))
    )
    (net (code "190") (name "unconnected-(J1-Pad240)") (class "Default")
      (node (ref "J1") (pin "240") (pinfunction "240_240") (pintype "passive"))
    )
    (net (code "191") (name "unconnected-(J1B-SHIELD-PadS1)") (class "Default")
      (node (ref "J1") (pin "S1") (pinfunction "SHIELD_S1") (pintype "passive"))
    )
  )
)
